# geiger.net
KiCad netlist of a schematic drawn in EAGLE
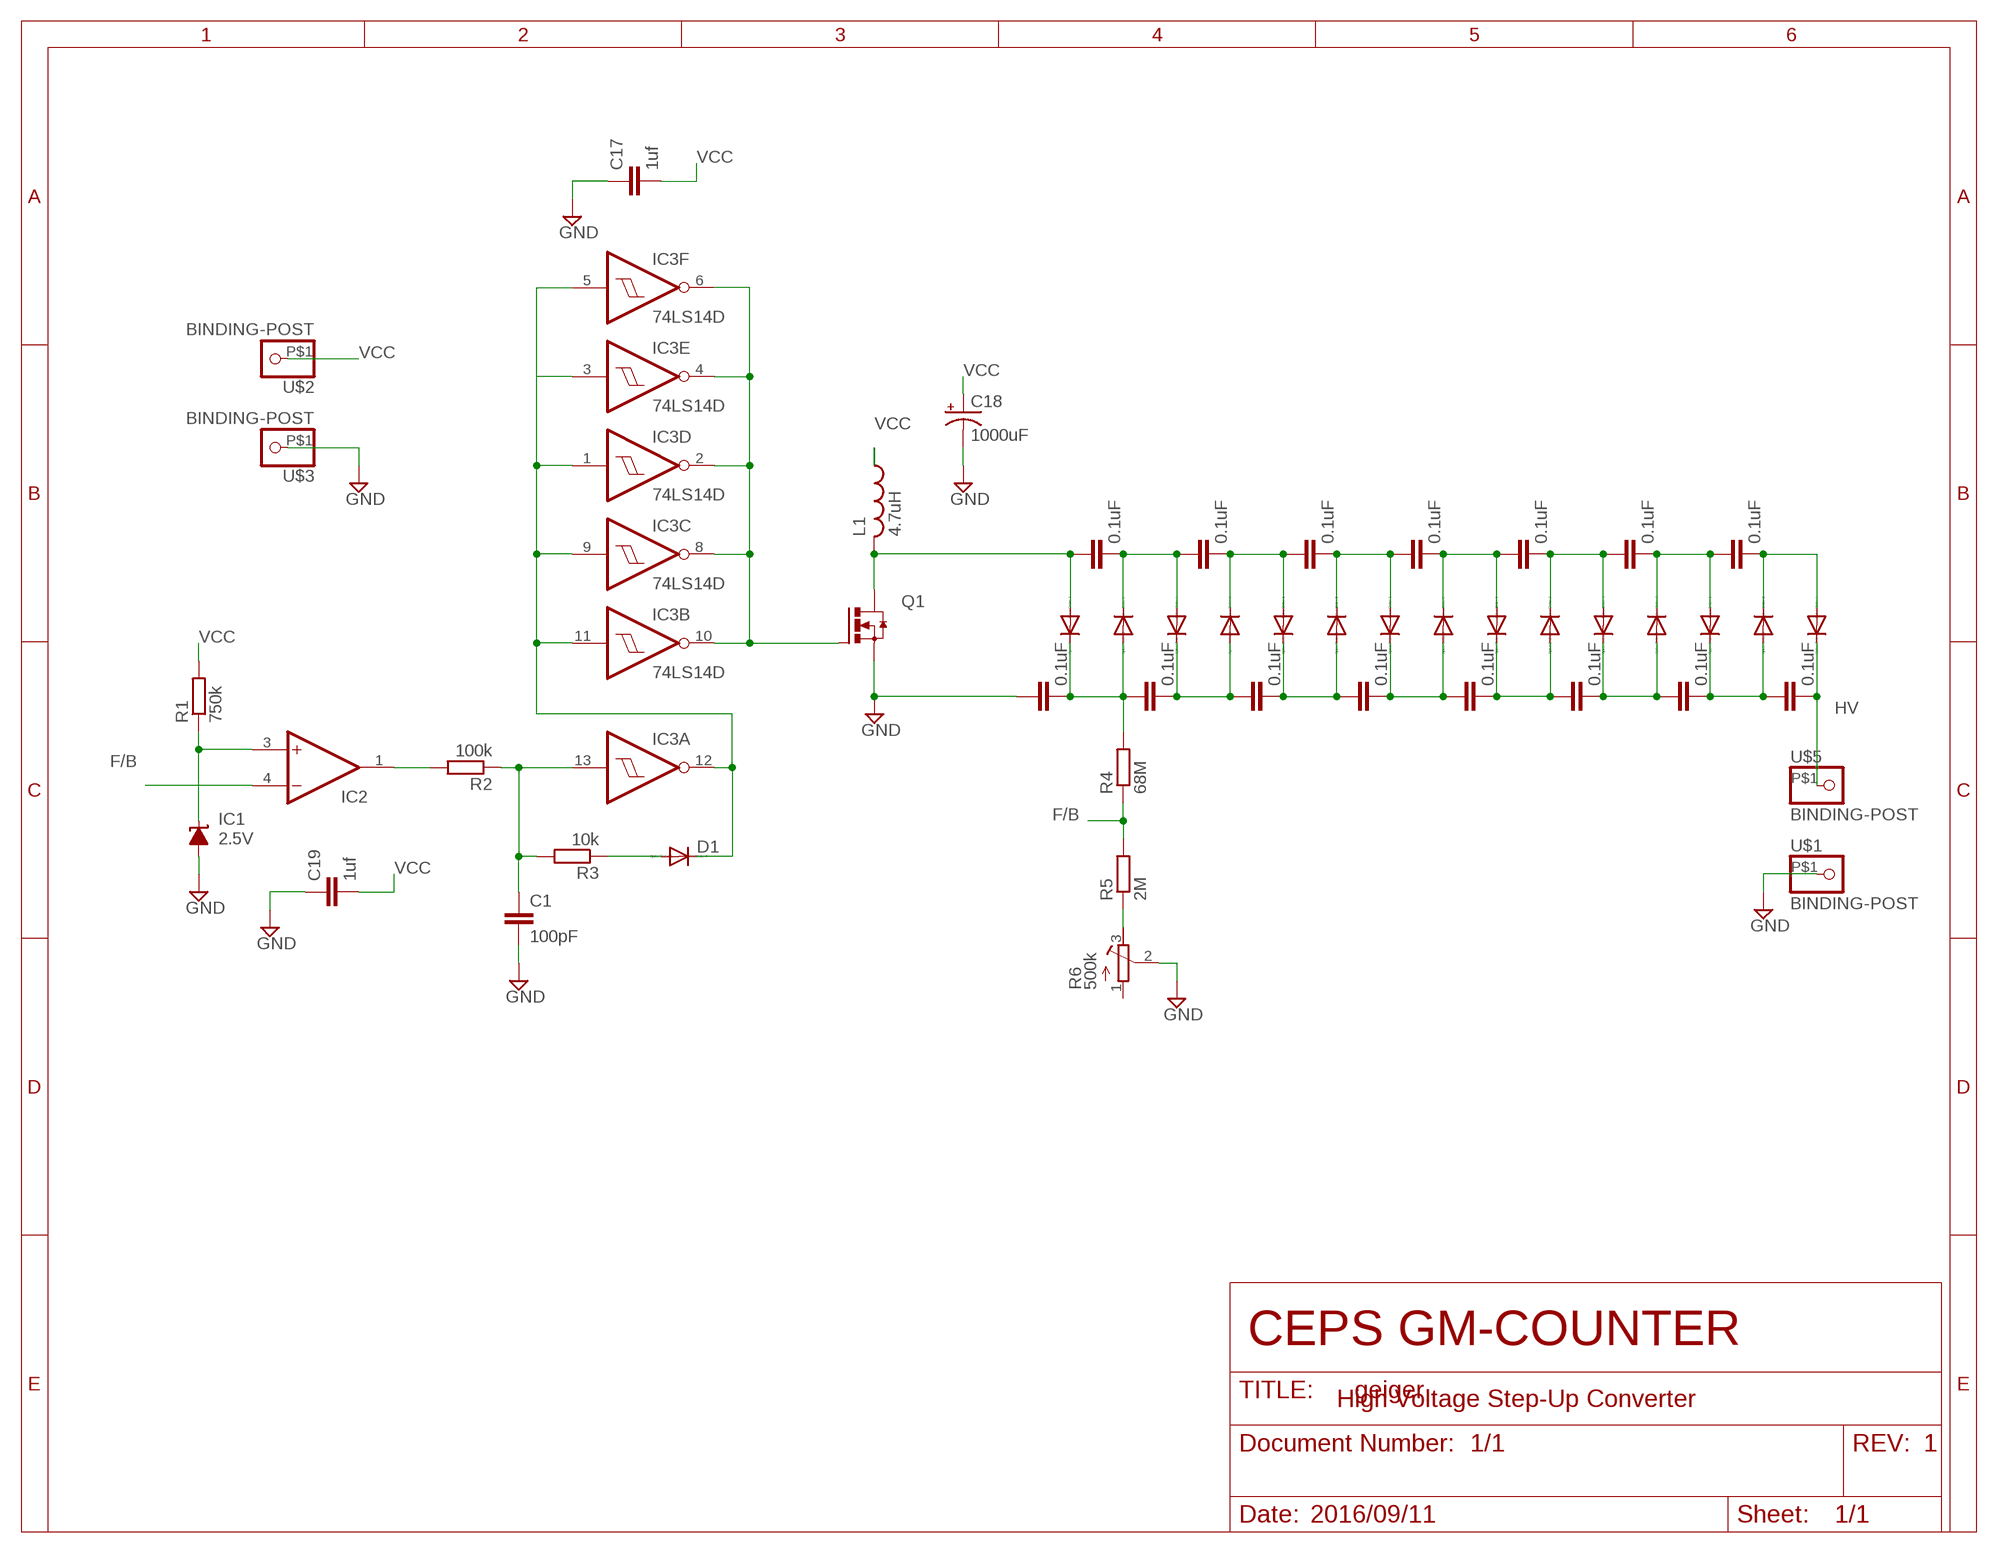
[diagram p0: schematic, sheet 1]

(export (version "E")
  (design (tool "Eeschema 10.0.6"))
  (components
    (comp (ref "C1")
      (value "100pF")
      (footprint "eagle-import:C0603")
      (libsource (lib "eagle-import") (part "C-EUC0603"))
    )
    (comp (ref "C2")
      (value "0.1uF")
      (footprint "eagle-import:C0603")
      (libsource (lib "eagle-import") (part "C-EUC0603"))
    )
    (comp (ref "C3")
      (value "0.1uF")
      (footprint "eagle-import:C0603")
      (libsource (lib "eagle-import") (part "C-EUC0603"))
    )
    (comp (ref "C4")
      (value "0.1uF")
      (footprint "eagle-import:C0603")
      (libsource (lib "eagle-import") (part "C-EUC0603"))
    )
    (comp (ref "C5")
      (value "0.1uF")
      (footprint "eagle-import:C0603")
      (libsource (lib "eagle-import") (part "C-EUC0603"))
    )
    (comp (ref "C6")
      (value "0.1uF")
      (footprint "eagle-import:C0603")
      (libsource (lib "eagle-import") (part "C-EUC0603"))
    )
    (comp (ref "C7")
      (value "0.1uF")
      (footprint "eagle-import:C0603")
      (libsource (lib "eagle-import") (part "C-EUC0603"))
    )
    (comp (ref "C8")
      (value "0.1uF")
      (footprint "eagle-import:C0603")
      (libsource (lib "eagle-import") (part "C-EUC0603"))
    )
    (comp (ref "C9")
      (value "0.1uF")
      (footprint "eagle-import:C0603")
      (libsource (lib "eagle-import") (part "C-EUC0603"))
    )
    (comp (ref "C10")
      (value "0.1uF")
      (footprint "eagle-import:C0603")
      (libsource (lib "eagle-import") (part "C-EUC0603"))
    )
    (comp (ref "C11")
      (value "0.1uF")
      (footprint "eagle-import:C0603")
      (libsource (lib "eagle-import") (part "C-EUC0603"))
    )
    (comp (ref "C12")
      (value "0.1uF")
      (footprint "eagle-import:C0603")
      (libsource (lib "eagle-import") (part "C-EUC0603"))
    )
    (comp (ref "C13")
      (value "0.1uF")
      (footprint "eagle-import:C0603")
      (libsource (lib "eagle-import") (part "C-EUC0603"))
    )
    (comp (ref "C14")
      (value "0.1uF")
      (footprint "eagle-import:C0603")
      (libsource (lib "eagle-import") (part "C-EUC0603"))
    )
    (comp (ref "C15")
      (value "0.1uF")
      (footprint "eagle-import:C0603")
      (libsource (lib "eagle-import") (part "C-EUC0603"))
    )
    (comp (ref "C16")
      (value "0.1uF")
      (footprint "eagle-import:C0603")
      (libsource (lib "eagle-import") (part "C-EUC0603"))
    )
    (comp (ref "C17")
      (value "1uf")
      (footprint "eagle-import:C0603")
      (libsource (lib "eagle-import") (part "C-EUC0603"))
    )
    (comp (ref "C18")
      (value "1000uF")
      (footprint "eagle-import:TT5D10")
      (libsource (lib "eagle-import") (part "CPOL-USTT5D10"))
    )
    (comp (ref "C19")
      (value "1uf")
      (footprint "eagle-import:C0603")
      (libsource (lib "eagle-import") (part "C-EUC0603"))
    )
    (comp (ref "D1")
      (value "1N4148DO35-7")
      (footprint "eagle-import:DO35-7")
      (libsource (lib "eagle-import") (part "1N4148DO35-7"))
    )
    (comp (ref "D2")
      (value "1N4148DO35-7")
      (footprint "eagle-import:DO35-7")
      (libsource (lib "eagle-import") (part "1N4148DO35-7"))
    )
    (comp (ref "D3")
      (value "1N4148DO35-7")
      (footprint "eagle-import:DO35-7")
      (libsource (lib "eagle-import") (part "1N4148DO35-7"))
    )
    (comp (ref "D4")
      (value "1N4148DO35-7")
      (footprint "eagle-import:DO35-7")
      (libsource (lib "eagle-import") (part "1N4148DO35-7"))
    )
    (comp (ref "D5")
      (value "1N4148DO35-7")
      (footprint "eagle-import:DO35-7")
      (libsource (lib "eagle-import") (part "1N4148DO35-7"))
    )
    (comp (ref "D6")
      (value "1N4148DO35-7")
      (footprint "eagle-import:DO35-7")
      (libsource (lib "eagle-import") (part "1N4148DO35-7"))
    )
    (comp (ref "D7")
      (value "1N4148DO35-7")
      (footprint "eagle-import:DO35-7")
      (libsource (lib "eagle-import") (part "1N4148DO35-7"))
    )
    (comp (ref "D8")
      (value "1N4148DO35-7")
      (footprint "eagle-import:DO35-7")
      (libsource (lib "eagle-import") (part "1N4148DO35-7"))
    )
    (comp (ref "D9")
      (value "1N4148DO35-7")
      (footprint "eagle-import:DO35-7")
      (libsource (lib "eagle-import") (part "1N4148DO35-7"))
    )
    (comp (ref "D10")
      (value "1N4148DO35-7")
      (footprint "eagle-import:DO35-7")
      (libsource (lib "eagle-import") (part "1N4148DO35-7"))
    )
    (comp (ref "D11")
      (value "1N4148DO35-7")
      (footprint "eagle-import:DO35-7")
      (libsource (lib "eagle-import") (part "1N4148DO35-7"))
    )
    (comp (ref "D12")
      (value "1N4148DO35-7")
      (footprint "eagle-import:DO35-7")
      (libsource (lib "eagle-import") (part "1N4148DO35-7"))
    )
    (comp (ref "D13")
      (value "1N4148DO35-7")
      (footprint "eagle-import:DO35-7")
      (libsource (lib "eagle-import") (part "1N4148DO35-7"))
    )
    (comp (ref "D14")
      (value "1N4148DO35-7")
      (footprint "eagle-import:DO35-7")
      (libsource (lib "eagle-import") (part "1N4148DO35-7"))
    )
    (comp (ref "D15")
      (value "1N4148DO35-7")
      (footprint "eagle-import:DO35-7")
      (libsource (lib "eagle-import") (part "1N4148DO35-7"))
    )
    (comp (ref "D16")
      (value "1N4148DO35-7")
      (footprint "eagle-import:DO35-7")
      (libsource (lib "eagle-import") (part "1N4148DO35-7"))
    )
    (comp (ref "IC1")
      (value "2.5V")
      (footprint "eagle-import:DBZ_R-PDSO-G3")
      (fields (field (name "MPN") "LM4041A12IDBZR"))
      (libsource (lib "eagle-import") (part "LM4041DBZA12"))
    )
    (comp (ref "IC2")
      (value "MAX4105EUK")
      (footprint "eagle-import:SOT23-5L")
      (fields (field (name "MPN") "MAX4105EUK+T"))
      (libsource (lib "eagle-import") (part "MAX4105EUK"))
    )
    (comp (ref "IC3")
      (value "74LS14D")
      (footprint "eagle-import:SO14")
      (libsource (lib "eagle-import") (part "7414DLS"))
    )
    (comp (ref "L1")
      (value "4.7uH")
      (footprint "eagle-import:6000-XXXX-RC")
      (libsource (lib "eagle-import") (part "L-US6000-XXX-RC"))
    )
    (comp (ref "Q1")
      (value "N-HEXFET-2D_SOT232-IRLL2705")
      (footprint "eagle-import:SOT223")
      (libsource (lib "eagle-import") (part "N-HEXFET-2D_?-SOT232IRLL2705"))
    )
    (comp (ref "R1")
      (value "750k")
      (footprint "eagle-import:R0603")
      (libsource (lib "eagle-import") (part "R-EU_R0603"))
    )
    (comp (ref "R2")
      (value "100k")
      (footprint "eagle-import:R0603")
      (libsource (lib "eagle-import") (part "R-EU_R0603"))
    )
    (comp (ref "R3")
      (value "10k")
      (footprint "eagle-import:R0603")
      (libsource (lib "eagle-import") (part "R-EU_R0603"))
    )
    (comp (ref "R4")
      (value "68M")
      (footprint "eagle-import:R0603")
      (libsource (lib "eagle-import") (part "R-EU_R0603"))
    )
    (comp (ref "R5")
      (value "2M")
      (footprint "eagle-import:R0603")
      (libsource (lib "eagle-import") (part "R-EU_R0603"))
    )
    (comp (ref "R6")
      (value "500k")
      (footprint "eagle-import:RTRIM4G_J")
      (libsource (lib "eagle-import") (part "R-TRIMM4G/J"))
    )
    (comp (ref "U$1")
      (value "BINDING-POST")
      (footprint "eagle-import:BINDING-POST")
      (libsource (lib "eagle-import") (part "BINDING-POST"))
    )
    (comp (ref "U$2")
      (value "BINDING-POST")
      (footprint "eagle-import:BINDING-POST")
      (libsource (lib "eagle-import") (part "BINDING-POST"))
    )
    (comp (ref "U$3")
      (value "BINDING-POST")
      (footprint "eagle-import:BINDING-POST")
      (libsource (lib "eagle-import") (part "BINDING-POST"))
    )
    (comp (ref "U$5")
      (value "BINDING-POST")
      (footprint "eagle-import:BINDING-POST")
      (libsource (lib "eagle-import") (part "BINDING-POST"))
    )
  )
  (nets
    (net (code "1") (name "/F{slash}B") (class "Default")
      (node (ref "IC2") (pin "4") (pinfunction "-IN_4") (pintype "input"))
      (node (ref "R4") (pin "1") (pinfunction "1_1") (pintype "passive"))
      (node (ref "R5") (pin "2") (pinfunction "2_2") (pintype "passive"))
    )
    (net (code "2") (name "/HV") (class "Default")
      (node (ref "C16") (pin "2") (pinfunction "2_2") (pintype "passive"))
      (node (ref "D16") (pin "C") (pinfunction "C_C") (pintype "passive"))
      (node (ref "U$5") (pin "P$1") (pinfunction "1_P$1") (pintype "passive"))
    )
    (net (code "3") (name "/VCC") (class "Default")
      (node (ref "C17") (pin "2") (pinfunction "2_2") (pintype "passive"))
      (node (ref "C18") (pin "+") (pinfunction "+_+") (pintype "passive"))
      (node (ref "C19") (pin "2") (pinfunction "2_2") (pintype "passive"))
      (node (ref "L1") (pin "1") (pinfunction "1_1") (pintype "passive"))
      (node (ref "R1") (pin "2") (pinfunction "2_2") (pintype "passive"))
      (node (ref "U$2") (pin "P$1") (pinfunction "1_P$1") (pintype "passive"))
    )
    (net (code "4") (name "GND") (class "Default")
      (node (ref "C1") (pin "2") (pinfunction "2_2") (pintype "passive"))
      (node (ref "C17") (pin "1") (pinfunction "1_1") (pintype "passive"))
      (node (ref "C18") (pin "-") (pinfunction "-_-") (pintype "passive"))
      (node (ref "C19") (pin "1") (pinfunction "1_1") (pintype "passive"))
      (node (ref "C2") (pin "1") (pinfunction "1_1") (pintype "passive"))
      (node (ref "IC1") (pin "2") (pinfunction "A_2") (pintype "passive"))
      (node (ref "Q1") (pin "3") (pinfunction "S_3") (pintype "passive"))
      (node (ref "R6") (pin "2") (pinfunction "S_2") (pintype "passive"))
      (node (ref "U$1") (pin "P$1") (pinfunction "1_P$1") (pintype "passive"))
      (node (ref "U$3") (pin "P$1") (pinfunction "1_P$1") (pintype "passive"))
    )
    (net (code "5") (name "Net-(C2-Pad2)") (class "Default")
      (node (ref "C2") (pin "2") (pinfunction "2_2") (pintype "passive"))
      (node (ref "C4") (pin "1") (pinfunction "1_1") (pintype "passive"))
      (node (ref "D2") (pin "C") (pinfunction "C_C") (pintype "passive"))
      (node (ref "D3") (pin "A") (pinfunction "A_A") (pintype "passive"))
      (node (ref "R4") (pin "2") (pinfunction "2_2") (pintype "passive"))
    )
    (net (code "6") (name "Net-(C3-Pad1)") (class "Default")
      (node (ref "C3") (pin "1") (pinfunction "1_1") (pintype "passive"))
      (node (ref "D2") (pin "A") (pinfunction "A_A") (pintype "passive"))
      (node (ref "L1") (pin "2") (pinfunction "2_2") (pintype "passive"))
      (node (ref "Q1") (pin "2") (pinfunction "D_2") (pintype "passive"))
      (node (ref "Q1") (pin "4") (pinfunction "D_4") (pintype "passive"))
    )
    (net (code "7") (name "Net-(C3-Pad2)") (class "Default")
      (node (ref "C3") (pin "2") (pinfunction "2_2") (pintype "passive"))
      (node (ref "C5") (pin "1") (pinfunction "1_1") (pintype "passive"))
      (node (ref "D3") (pin "C") (pinfunction "C_C") (pintype "passive"))
      (node (ref "D4") (pin "A") (pinfunction "A_A") (pintype "passive"))
    )
    (net (code "8") (name "Net-(C4-Pad2)") (class "Default")
      (node (ref "C4") (pin "2") (pinfunction "2_2") (pintype "passive"))
      (node (ref "C6") (pin "1") (pinfunction "1_1") (pintype "passive"))
      (node (ref "D4") (pin "C") (pinfunction "C_C") (pintype "passive"))
      (node (ref "D5") (pin "A") (pinfunction "A_A") (pintype "passive"))
    )
    (net (code "9") (name "Net-(C5-Pad2)") (class "Default")
      (node (ref "C5") (pin "2") (pinfunction "2_2") (pintype "passive"))
      (node (ref "C7") (pin "1") (pinfunction "1_1") (pintype "passive"))
      (node (ref "D5") (pin "C") (pinfunction "C_C") (pintype "passive"))
      (node (ref "D6") (pin "A") (pinfunction "A_A") (pintype "passive"))
    )
    (net (code "10") (name "Net-(C6-Pad2)") (class "Default")
      (node (ref "C6") (pin "2") (pinfunction "2_2") (pintype "passive"))
      (node (ref "C8") (pin "1") (pinfunction "1_1") (pintype "passive"))
      (node (ref "D6") (pin "C") (pinfunction "C_C") (pintype "passive"))
      (node (ref "D7") (pin "A") (pinfunction "A_A") (pintype "passive"))
    )
    (net (code "11") (name "Net-(C7-Pad2)") (class "Default")
      (node (ref "C7") (pin "2") (pinfunction "2_2") (pintype "passive"))
      (node (ref "C9") (pin "1") (pinfunction "1_1") (pintype "passive"))
      (node (ref "D7") (pin "C") (pinfunction "C_C") (pintype "passive"))
      (node (ref "D8") (pin "A") (pinfunction "A_A") (pintype "passive"))
    )
    (net (code "12") (name "Net-(C10-Pad1)") (class "Default")
      (node (ref "C10") (pin "1") (pinfunction "1_1") (pintype "passive"))
      (node (ref "C8") (pin "2") (pinfunction "2_2") (pintype "passive"))
      (node (ref "D8") (pin "C") (pinfunction "C_C") (pintype "passive"))
      (node (ref "D9") (pin "A") (pinfunction "A_A") (pintype "passive"))
    )
    (net (code "13") (name "Net-(C10-Pad2)") (class "Default")
      (node (ref "C10") (pin "2") (pinfunction "2_2") (pintype "passive"))
      (node (ref "C12") (pin "1") (pinfunction "1_1") (pintype "passive"))
      (node (ref "D10") (pin "C") (pinfunction "C_C") (pintype "passive"))
      (node (ref "D11") (pin "A") (pinfunction "A_A") (pintype "passive"))
    )
    (net (code "14") (name "Net-(C11-Pad1)") (class "Default")
      (node (ref "C11") (pin "1") (pinfunction "1_1") (pintype "passive"))
      (node (ref "C9") (pin "2") (pinfunction "2_2") (pintype "passive"))
      (node (ref "D10") (pin "A") (pinfunction "A_A") (pintype "passive"))
      (node (ref "D9") (pin "C") (pinfunction "C_C") (pintype "passive"))
    )
    (net (code "15") (name "Net-(C11-Pad2)") (class "Default")
      (node (ref "C11") (pin "2") (pinfunction "2_2") (pintype "passive"))
      (node (ref "C13") (pin "1") (pinfunction "1_1") (pintype "passive"))
      (node (ref "D11") (pin "C") (pinfunction "C_C") (pintype "passive"))
      (node (ref "D12") (pin "A") (pinfunction "A_A") (pintype "passive"))
    )
    (net (code "16") (name "Net-(C12-Pad2)") (class "Default")
      (node (ref "C12") (pin "2") (pinfunction "2_2") (pintype "passive"))
      (node (ref "C14") (pin "1") (pinfunction "1_1") (pintype "passive"))
      (node (ref "D12") (pin "C") (pinfunction "C_C") (pintype "passive"))
      (node (ref "D13") (pin "A") (pinfunction "A_A") (pintype "passive"))
    )
    (net (code "17") (name "Net-(C13-Pad2)") (class "Default")
      (node (ref "C13") (pin "2") (pinfunction "2_2") (pintype "passive"))
      (node (ref "C15") (pin "1") (pinfunction "1_1") (pintype "passive"))
      (node (ref "D13") (pin "C") (pinfunction "C_C") (pintype "passive"))
      (node (ref "D14") (pin "A") (pinfunction "A_A") (pintype "passive"))
    )
    (net (code "18") (name "Net-(C14-Pad2)") (class "Default")
      (node (ref "C14") (pin "2") (pinfunction "2_2") (pintype "passive"))
      (node (ref "C16") (pin "1") (pinfunction "1_1") (pintype "passive"))
      (node (ref "D14") (pin "C") (pinfunction "C_C") (pintype "passive"))
      (node (ref "D15") (pin "A") (pinfunction "A_A") (pintype "passive"))
    )
    (net (code "19") (name "Net-(C15-Pad2)") (class "Default")
      (node (ref "C15") (pin "2") (pinfunction "2_2") (pintype "passive"))
      (node (ref "D15") (pin "C") (pinfunction "C_C") (pintype "passive"))
      (node (ref "D16") (pin "A") (pinfunction "A_A") (pintype "passive"))
    )
    (net (code "20") (name "Net-(D1-PadA)") (class "Default")
      (node (ref "D1") (pin "A") (pinfunction "A_A") (pintype "passive"))
      (node (ref "R3") (pin "1") (pinfunction "1_1") (pintype "passive"))
    )
    (net (code "21") (name "Net-(IC1-C)") (class "Default")
      (node (ref "IC1") (pin "1") (pinfunction "C_1") (pintype "passive"))
      (node (ref "IC2") (pin "3") (pinfunction "+IN_3") (pintype "input"))
      (node (ref "R1") (pin "1") (pinfunction "1_1") (pintype "passive"))
    )
    (net (code "22") (name "Net-(IC2A-OUT)") (class "Default")
      (node (ref "IC2") (pin "1") (pinfunction "OUT_1") (pintype "output"))
      (node (ref "R2") (pin "2") (pinfunction "2_2") (pintype "passive"))
    )
    (net (code "23") (name "Net-(IC3A-I)") (class "Default")
      (node (ref "C1") (pin "1") (pinfunction "1_1") (pintype "passive"))
      (node (ref "IC3") (pin "13") (pinfunction "I_13") (pintype "input"))
      (node (ref "R2") (pin "1") (pinfunction "1_1") (pintype "passive"))
      (node (ref "R3") (pin "2") (pinfunction "2_2") (pintype "passive"))
    )
    (net (code "24") (name "Net-(IC3A-O)") (class "Default")
      (node (ref "D1") (pin "C") (pinfunction "C_C") (pintype "passive"))
      (node (ref "IC3") (pin "1") (pinfunction "I_1") (pintype "input"))
      (node (ref "IC3") (pin "11") (pinfunction "I_11") (pintype "input"))
      (node (ref "IC3") (pin "12") (pinfunction "O_12") (pintype "output"))
      (node (ref "IC3") (pin "3") (pinfunction "I_3") (pintype "input"))
      (node (ref "IC3") (pin "5") (pinfunction "I_5") (pintype "input"))
      (node (ref "IC3") (pin "9") (pinfunction "I_9") (pintype "input"))
    )
    (net (code "25") (name "Net-(IC3B-O)") (class "Default")
      (node (ref "IC3") (pin "10") (pinfunction "O_10") (pintype "output"))
      (node (ref "IC3") (pin "2") (pinfunction "O_2") (pintype "output"))
      (node (ref "IC3") (pin "4") (pinfunction "O_4") (pintype "output"))
      (node (ref "IC3") (pin "6") (pinfunction "O_6") (pintype "output"))
      (node (ref "IC3") (pin "8") (pinfunction "O_8") (pintype "output"))
      (node (ref "Q1") (pin "1") (pinfunction "G_1") (pintype "passive"))
    )
    (net (code "26") (name "Net-(R6-E)") (class "Default")
      (node (ref "R5") (pin "1") (pinfunction "1_1") (pintype "passive"))
      (node (ref "R6") (pin "3") (pinfunction "E_3") (pintype "passive"))
    )
    (net (code "27") (name "unconnected-(R6-A-Pad1)") (class "Default")
      (node (ref "R6") (pin "1") (pinfunction "A_1") (pintype "passive"))
    )
  )
)
